# Supply_for_adums.net
KiCad netlist of a schematic drawn in Altium Designer
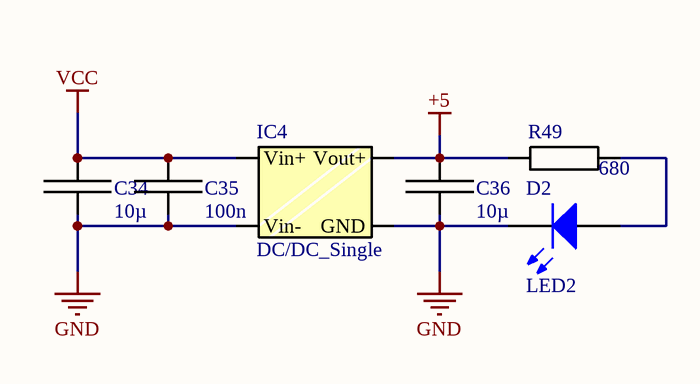
[diagram p0: Supply_for_adums.SchDoc]

(export (version "E")
  (design (tool "Eeschema 10.0.6"))
  (components
    (comp (ref "C34")
      (value "10µ")
      (footprint "RLC_0805")
      (libsource (lib "PRJ_LIB_LTC2983_Card") (part "C"))
    )
    (comp (ref "C35")
      (value "100n")
      (footprint "RLC_0805")
      (libsource (lib "PRJ_LIB_LTC2983_Card") (part "C"))
    )
    (comp (ref "C36")
      (value "10µ")
      (footprint "RLC_0805")
      (libsource (lib "PRJ_LIB_LTC2983_Card") (part "C"))
    )
    (comp (ref "D2")
      (value "LED2")
      (footprint "3.2X1.6X1.1")
      (description "Typical RED, GREEN, YELLOW, AMBER GaAs LED")
      (fields (field (name "PUBLISHER") "Altium Limited"))
      (libsource (lib "Miscellaneous Devices") (part "LED2"))
    )
    (comp (ref "IC4")
      (value "DC/DC_Single")
      (footprint "SIP4DCDC")
      (libsource (lib "PRJ_LIB_LTC2983_Card") (part "DC/DC_Single"))
    )
    (comp (ref "R49")
      (value "680")
      (footprint "RLC_0805")
      (libsource (lib "PRJ_LIB_LTC2983_Card") (part "R"))
    )
  )
  (nets
    (net (code "1") (name "+5") (class "Default")
      (node (ref "C36") (pin "1") (pinfunction "1_1") (pintype "passive"))
      (node (ref "IC4") (pin "6") (pinfunction "Vout+_6") (pintype "passive"))
      (node (ref "R49") (pin "1") (pinfunction "1_1") (pintype "passive"))
    )
    (net (code "2") (name "GND") (class "Default")
      (node (ref "C34") (pin "2") (pinfunction "2_2") (pintype "passive"))
      (node (ref "C35") (pin "2") (pinfunction "2_2") (pintype "passive"))
      (node (ref "C36") (pin "2") (pinfunction "2_2") (pintype "passive"))
      (node (ref "D2") (pin "2") (pinfunction "K_2") (pintype "passive"))
      (node (ref "IC4") (pin "2") (pinfunction "Vin-_2") (pintype "passive"))
      (node (ref "IC4") (pin "4") (pinfunction "GND_4") (pintype "passive"))
    )
    (net (code "3") (name "Net-(D2-A)") (class "Default")
      (node (ref "D2") (pin "1") (pinfunction "A_1") (pintype "passive"))
      (node (ref "R49") (pin "2") (pinfunction "2_2") (pintype "passive"))
    )
    (net (code "4") (name "VCC") (class "Default")
      (node (ref "C34") (pin "1") (pinfunction "1_1") (pintype "passive"))
      (node (ref "C35") (pin "1") (pinfunction "1_1") (pintype "passive"))
      (node (ref "IC4") (pin "1") (pinfunction "Vin+_1") (pintype "passive"))
    )
  )
)
